# Relay.net
KiCad netlist of a schematic drawn in Altium Designer
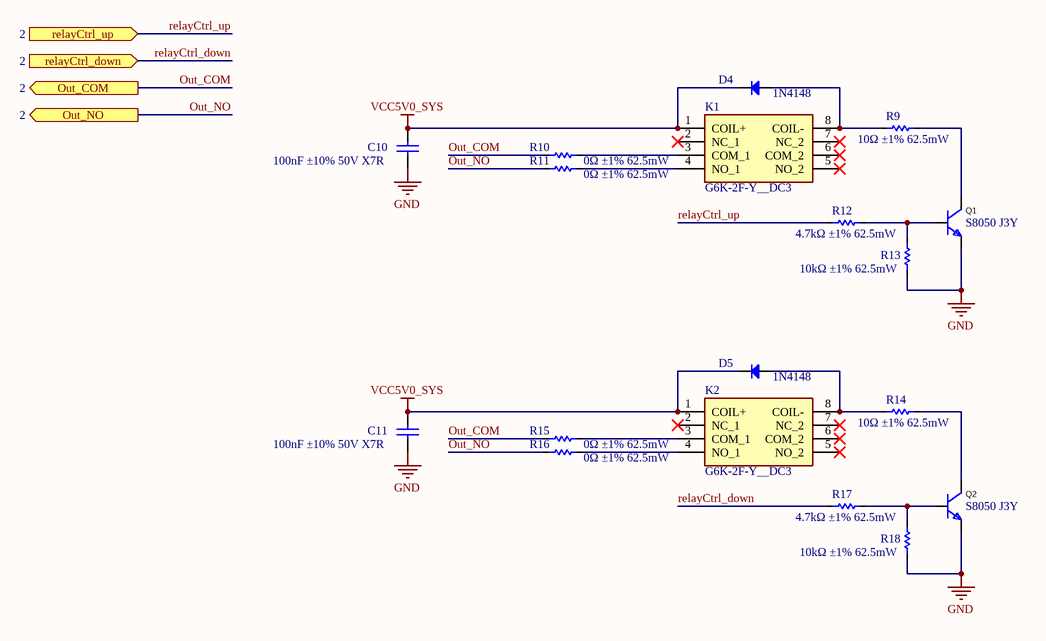
[diagram p0: Relay.SchDoc]

(export (version "E")
  (design (tool "Eeschema 10.0.6"))
  (components
    (comp (ref "C10")
      (value "100nF ±10% 50V X7R")
      (footprint "C0603")
      (description "CC0603KRX7R9BB104")
      (fields (field (name "PUBLISHER") "Altium Limited"))
      (libsource (lib "Component") (part "C0603"))
    )
    (comp (ref "C11")
      (value "100nF ±10% 50V X7R")
      (footprint "C0603")
      (description "CC0603KRX7R9BB104")
      (fields (field (name "PUBLISHER") "Altium Limited"))
      (libsource (lib "Component") (part "C0603"))
    )
    (comp (ref "D4")
      (value "1N4148")
      (footprint "SMA_L4.3-W2.6-LS5.2-RD")
      (description "High Conductance Fast Diode")
      (fields (field (name "PUBLISHER") "Altium Limited"))
      (libsource (lib "Component") (part "Diode"))
    )
    (comp (ref "D5")
      (value "1N4148")
      (footprint "SMA_L4.3-W2.6-LS5.2-RD")
      (description "High Conductance Fast Diode")
      (fields (field (name "PUBLISHER") "Altium Limited"))
      (libsource (lib "Component") (part "Diode"))
    )
    (comp (ref "K1")
      (value "G6K-2F-Y__DC3")
      (footprint "SamacSys:G6K2FYDC3")
      (description "Relay or Contactor")
      (fields (field (name "MANUFACTURER_PART_NUMBER") "G6K-2F-Y  DC3"))
      (libsource (lib "*") (part "G6K-2F-Y__DC3"))
    )
    (comp (ref "K2")
      (value "G6K-2F-Y__DC3")
      (footprint "SamacSys:G6K2FYDC3")
      (description "Relay or Contactor")
      (fields (field (name "MANUFACTURER_PART_NUMBER") "G6K-2F-Y  DC3"))
      (libsource (lib "*") (part "G6K-2F-Y__DC3"))
    )
    (comp (ref "Q1")
      (value "S8050 J3Y")
      (footprint "SOT95P240X110-3N")
      (fields (field (name "MANUFACTURER") "CJ(江苏长电/长晶)") (field (name "MANUFACTURER PART") "SS8050"))
      (libsource (lib "Component") (part "S8050"))
    )
    (comp (ref "Q2")
      (value "S8050 J3Y")
      (footprint "SOT95P240X110-3N")
      (fields (field (name "MANUFACTURER") "CJ(江苏长电/长晶)") (field (name "MANUFACTURER PART") "SS8050"))
      (libsource (lib "Component") (part "S8050"))
    )
    (comp (ref "R9")
      (value "10Ω ±1% 62.5mW")
      (footprint "R0402")
      (description "Resistor")
      (fields (field (name "PUBLISHER") "Altium Limited"))
      (libsource (lib "Component") (part "R0402"))
    )
    (comp (ref "R10")
      (value "0Ω ±1% 62.5mW")
      (footprint "R0402")
      (description "Resistor")
      (fields (field (name "PUBLISHER") "Altium Limited"))
      (libsource (lib "Component") (part "R0402"))
    )
    (comp (ref "R11")
      (value "0Ω ±1% 62.5mW")
      (footprint "R0402")
      (description "Resistor")
      (fields (field (name "PUBLISHER") "Altium Limited"))
      (libsource (lib "Component") (part "R0402"))
    )
    (comp (ref "R12")
      (value "4.7kΩ ±1% 62.5mW")
      (footprint "R0402")
      (description "Resistor")
      (fields (field (name "PUBLISHER") "Altium Limited"))
      (libsource (lib "Component") (part "R0402"))
    )
    (comp (ref "R13")
      (value "10kΩ ±1% 62.5mW")
      (footprint "R0402")
      (description "Resistor")
      (fields (field (name "PUBLISHER") "Altium Limited"))
      (libsource (lib "Component") (part "R0402"))
    )
    (comp (ref "R14")
      (value "10Ω ±1% 62.5mW")
      (footprint "R0402")
      (description "Resistor")
      (fields (field (name "PUBLISHER") "Altium Limited"))
      (libsource (lib "Component") (part "R0402"))
    )
    (comp (ref "R15")
      (value "0Ω ±1% 62.5mW")
      (footprint "R0402")
      (description "Resistor")
      (fields (field (name "PUBLISHER") "Altium Limited"))
      (libsource (lib "Component") (part "R0402"))
    )
    (comp (ref "R16")
      (value "0Ω ±1% 62.5mW")
      (footprint "R0402")
      (description "Resistor")
      (fields (field (name "PUBLISHER") "Altium Limited"))
      (libsource (lib "Component") (part "R0402"))
    )
    (comp (ref "R17")
      (value "4.7kΩ ±1% 62.5mW")
      (footprint "R0402")
      (description "Resistor")
      (fields (field (name "PUBLISHER") "Altium Limited"))
      (libsource (lib "Component") (part "R0402"))
    )
    (comp (ref "R18")
      (value "10kΩ ±1% 62.5mW")
      (footprint "R0402")
      (description "Resistor")
      (fields (field (name "PUBLISHER") "Altium Limited"))
      (libsource (lib "Component") (part "R0402"))
    )
  )
  (nets
    (net (code "1") (name "/Out_COM") (class "Default")
      (node (ref "R10") (pin "2") (pinfunction "2_2") (pintype "passive"))
      (node (ref "R15") (pin "2") (pinfunction "2_2") (pintype "passive"))
    )
    (net (code "2") (name "/Out_NO") (class "Default")
      (node (ref "R11") (pin "2") (pinfunction "2_2") (pintype "passive"))
      (node (ref "R16") (pin "2") (pinfunction "2_2") (pintype "passive"))
    )
    (net (code "3") (name "/relayCtrl_down") (class "Default")
      (node (ref "R17") (pin "1") (pinfunction "1_1") (pintype "passive"))
    )
    (net (code "4") (name "/relayCtrl_up") (class "Default")
      (node (ref "R12") (pin "1") (pinfunction "1_1") (pintype "passive"))
    )
    (net (code "5") (name "GND") (class "Default")
      (node (ref "C10") (pin "1") (pinfunction "1_1") (pintype "passive"))
      (node (ref "C11") (pin "1") (pinfunction "1_1") (pintype "passive"))
      (node (ref "Q1") (pin "2") (pinfunction "E_2") (pintype "passive"))
      (node (ref "Q2") (pin "2") (pinfunction "E_2") (pintype "passive"))
      (node (ref "R13") (pin "1") (pinfunction "1_1") (pintype "passive"))
      (node (ref "R18") (pin "1") (pinfunction "1_1") (pintype "passive"))
    )
    (net (code "6") (name "Net-(D4-A)") (class "Default")
      (node (ref "D4") (pin "1") (pinfunction "A_1") (pintype "passive"))
      (node (ref "K1") (pin "8") (pinfunction "COIL-_8") (pintype "passive"))
      (node (ref "R9") (pin "2") (pinfunction "2_2") (pintype "passive"))
    )
    (net (code "7") (name "Net-(D5-A)") (class "Default")
      (node (ref "D5") (pin "1") (pinfunction "A_1") (pintype "passive"))
      (node (ref "K2") (pin "8") (pinfunction "COIL-_8") (pintype "passive"))
      (node (ref "R14") (pin "2") (pinfunction "2_2") (pintype "passive"))
    )
    (net (code "8") (name "Net-(K1-COM_1)") (class "Default")
      (node (ref "K1") (pin "3") (pinfunction "COM_1_3") (pintype "passive"))
      (node (ref "R10") (pin "1") (pinfunction "1_1") (pintype "passive"))
    )
    (net (code "9") (name "Net-(K1-NO_1)") (class "Default")
      (node (ref "K1") (pin "4") (pinfunction "NO_1_4") (pintype "passive"))
      (node (ref "R11") (pin "1") (pinfunction "1_1") (pintype "passive"))
    )
    (net (code "10") (name "Net-(K2-COM_1)") (class "Default")
      (node (ref "K2") (pin "3") (pinfunction "COM_1_3") (pintype "passive"))
      (node (ref "R15") (pin "1") (pinfunction "1_1") (pintype "passive"))
    )
    (net (code "11") (name "Net-(K2-NO_1)") (class "Default")
      (node (ref "K2") (pin "4") (pinfunction "NO_1_4") (pintype "passive"))
      (node (ref "R16") (pin "1") (pinfunction "1_1") (pintype "passive"))
    )
    (net (code "12") (name "Net-(Q1-B)") (class "Default")
      (node (ref "Q1") (pin "1") (pinfunction "B_1") (pintype "passive"))
      (node (ref "R12") (pin "2") (pinfunction "2_2") (pintype "passive"))
      (node (ref "R13") (pin "2") (pinfunction "2_2") (pintype "passive"))
    )
    (net (code "13") (name "Net-(Q1-C)") (class "Default")
      (node (ref "Q1") (pin "3") (pinfunction "C_3") (pintype "passive"))
      (node (ref "R9") (pin "1") (pinfunction "1_1") (pintype "passive"))
    )
    (net (code "14") (name "Net-(Q2-B)") (class "Default")
      (node (ref "Q2") (pin "1") (pinfunction "B_1") (pintype "passive"))
      (node (ref "R17") (pin "2") (pinfunction "2_2") (pintype "passive"))
      (node (ref "R18") (pin "2") (pinfunction "2_2") (pintype "passive"))
    )
    (net (code "15") (name "Net-(Q2-C)") (class "Default")
      (node (ref "Q2") (pin "3") (pinfunction "C_3") (pintype "passive"))
      (node (ref "R14") (pin "1") (pinfunction "1_1") (pintype "passive"))
    )
    (net (code "16") (name "VCC5V0_SYS") (class "Default")
      (node (ref "C10") (pin "2") (pinfunction "2_2") (pintype "passive"))
      (node (ref "C11") (pin "2") (pinfunction "2_2") (pintype "passive"))
      (node (ref "D4") (pin "2") (pinfunction "K_2") (pintype "passive"))
      (node (ref "D5") (pin "2") (pinfunction "K_2") (pintype "passive"))
      (node (ref "K1") (pin "1") (pinfunction "COIL+_1") (pintype "passive"))
      (node (ref "K2") (pin "1") (pinfunction "COIL+_1") (pintype "passive"))
    )
    (net (code "17") (name "unconnected-(K1-COM_2-Pad6)") (class "Default")
      (node (ref "K1") (pin "6") (pinfunction "COM_2_6") (pintype "passive+no_connect"))
    )
    (net (code "18") (name "unconnected-(K1-NC_1-Pad2)") (class "Default")
      (node (ref "K1") (pin "2") (pinfunction "NC_1_2") (pintype "passive+no_connect"))
    )
    (net (code "19") (name "unconnected-(K1-NC_2-Pad7)") (class "Default")
      (node (ref "K1") (pin "7") (pinfunction "NC_2_7") (pintype "passive+no_connect"))
    )
    (net (code "20") (name "unconnected-(K1-NO_2-Pad5)") (class "Default")
      (node (ref "K1") (pin "5") (pinfunction "NO_2_5") (pintype "passive+no_connect"))
    )
    (net (code "21") (name "unconnected-(K2-COM_2-Pad6)") (class "Default")
      (node (ref "K2") (pin "6") (pinfunction "COM_2_6") (pintype "passive+no_connect"))
    )
    (net (code "22") (name "unconnected-(K2-NC_1-Pad2)") (class "Default")
      (node (ref "K2") (pin "2") (pinfunction "NC_1_2") (pintype "passive+no_connect"))
    )
    (net (code "23") (name "unconnected-(K2-NC_2-Pad7)") (class "Default")
      (node (ref "K2") (pin "7") (pinfunction "NC_2_7") (pintype "passive+no_connect"))
    )
    (net (code "24") (name "unconnected-(K2-NO_2-Pad5)") (class "Default")
      (node (ref "K2") (pin "5") (pinfunction "NO_2_5") (pintype "passive+no_connect"))
    )
  )
)
